# LCD.net
KiCad netlist of a schematic drawn in Altium Designer
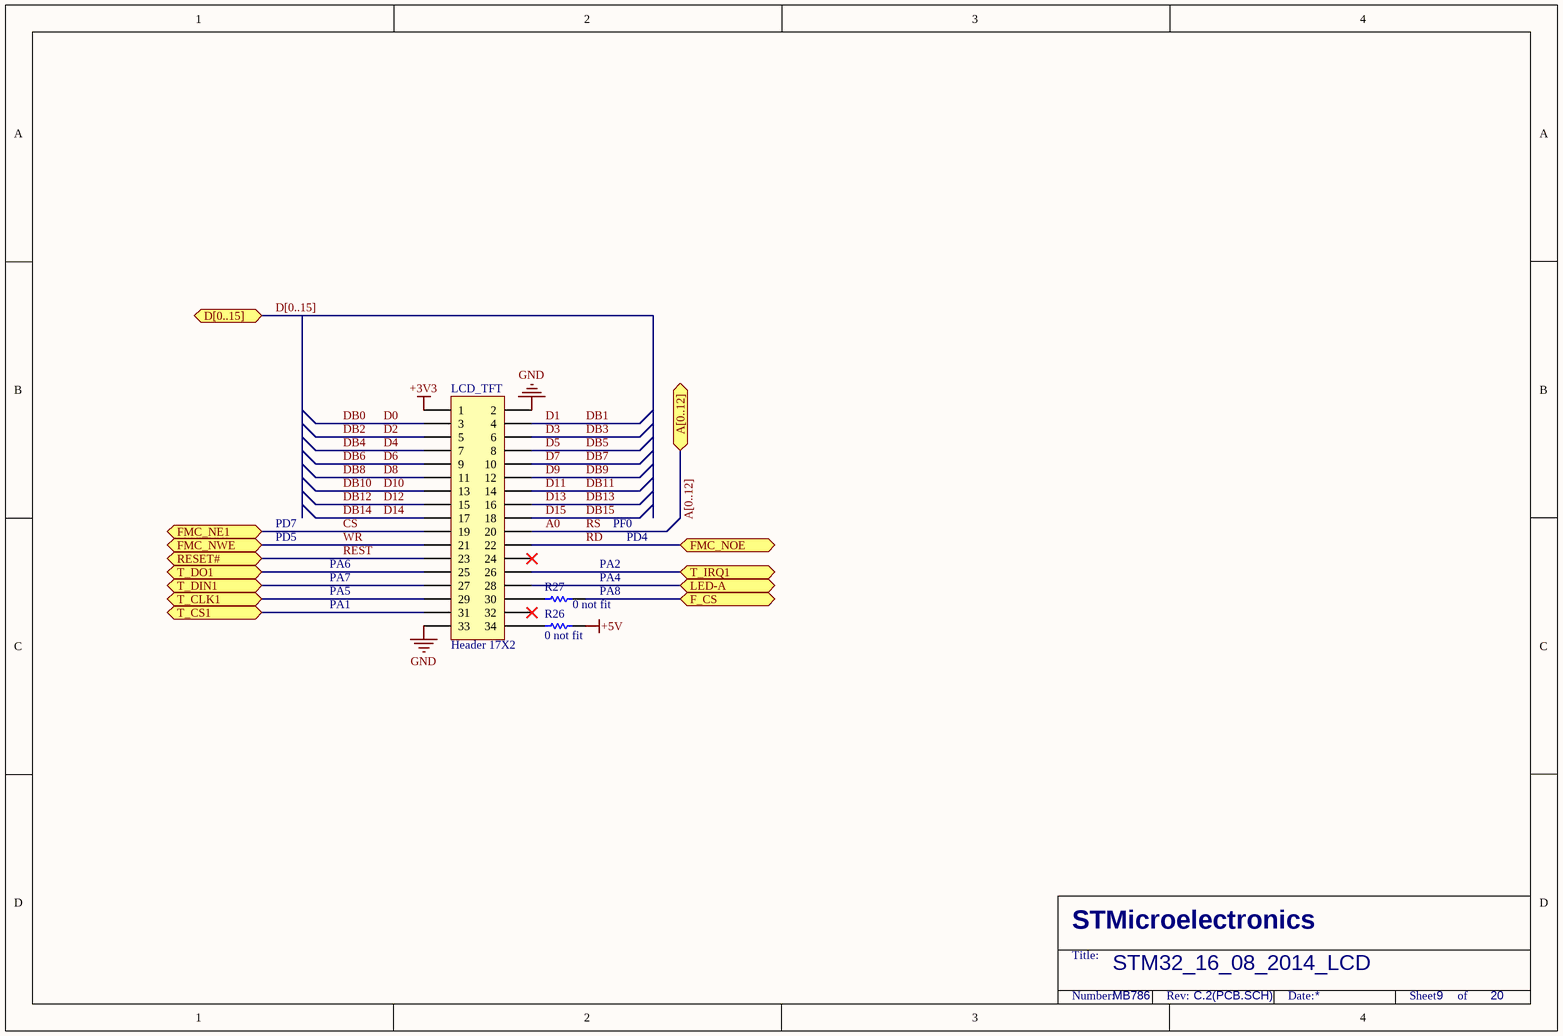
[diagram p0: LCD.SchDoc]

(export (version "E")
  (design (tool "Eeschema 10.0.6"))
  (components
    (comp (ref "LCD_TFT")
      (value "Header 17X2")
      (footprint "HDR2X17")
      (description "Header, 17-Pin, Dual row")
      (fields (field (name "PUBLISHER") "Altium Limited"))
      (libsource (lib "Miscellaneous Connectors") (part "Header 17X2"))
    )
    (comp (ref "R26")
      (value "0 not fit")
      (footprint "0603_R")
      (description "Resistor")
      (fields (field (name "PUBLISHER") "Altium Limited"))
      (libsource (lib "Miscellaneous Devices") (part "Res1"))
    )
    (comp (ref "R27")
      (value "0 not fit")
      (footprint "0603_R")
      (description "Resistor")
      (fields (field (name "PUBLISHER") "Altium Limited"))
      (libsource (lib "Miscellaneous Devices") (part "Res1"))
    )
  )
  (nets
    (net (code "13") (name "+3V3") (class "Default")
      (node (ref "LCD_TFT") (pin "1") (pinfunction "1_1") (pintype "passive"))
    )
    (net (code "14") (name "+5V") (class "Default")
      (node (ref "R26") (pin "1") (pinfunction "1_1") (pintype "passive"))
    )
    (net (code "15") (name "/A0") (class "Default")
      (node (ref "LCD_TFT") (pin "20") (pinfunction "20_20") (pintype "passive"))
    )
    (net (code "17") (name "/CS") (class "Default")
      (node (ref "LCD_TFT") (pin "19") (pinfunction "19_19") (pintype "passive"))
    )
    (net (code "18") (name "/D0") (class "Default")
      (node (ref "LCD_TFT") (pin "3") (pinfunction "3_3") (pintype "passive"))
    )
    (net (code "19") (name "/D1") (class "Default")
      (node (ref "LCD_TFT") (pin "4") (pinfunction "4_4") (pintype "passive"))
    )
    (net (code "20") (name "/D2") (class "Default")
      (node (ref "LCD_TFT") (pin "5") (pinfunction "5_5") (pintype "passive"))
    )
    (net (code "21") (name "/D3") (class "Default")
      (node (ref "LCD_TFT") (pin "6") (pinfunction "6_6") (pintype "passive"))
    )
    (net (code "22") (name "/D4") (class "Default")
      (node (ref "LCD_TFT") (pin "7") (pinfunction "7_7") (pintype "passive"))
    )
    (net (code "23") (name "/D5") (class "Default")
      (node (ref "LCD_TFT") (pin "8") (pinfunction "8_8") (pintype "passive"))
    )
    (net (code "24") (name "/D6") (class "Default")
      (node (ref "LCD_TFT") (pin "9") (pinfunction "9_9") (pintype "passive"))
    )
    (net (code "25") (name "/D7") (class "Default")
      (node (ref "LCD_TFT") (pin "10") (pinfunction "10_10") (pintype "passive"))
    )
    (net (code "26") (name "/D8") (class "Default")
      (node (ref "LCD_TFT") (pin "11") (pinfunction "11_11") (pintype "passive"))
    )
    (net (code "27") (name "/D9") (class "Default")
      (node (ref "LCD_TFT") (pin "12") (pinfunction "12_12") (pintype "passive"))
    )
    (net (code "28") (name "/D10") (class "Default")
      (node (ref "LCD_TFT") (pin "13") (pinfunction "13_13") (pintype "passive"))
    )
    (net (code "29") (name "/D11") (class "Default")
      (node (ref "LCD_TFT") (pin "14") (pinfunction "14_14") (pintype "passive"))
    )
    (net (code "30") (name "/D12") (class "Default")
      (node (ref "LCD_TFT") (pin "15") (pinfunction "15_15") (pintype "passive"))
    )
    (net (code "31") (name "/D13") (class "Default")
      (node (ref "LCD_TFT") (pin "16") (pinfunction "16_16") (pintype "passive"))
    )
    (net (code "32") (name "/D14") (class "Default")
      (node (ref "LCD_TFT") (pin "17") (pinfunction "17_17") (pintype "passive"))
    )
    (net (code "33") (name "/D15") (class "Default")
      (node (ref "LCD_TFT") (pin "18") (pinfunction "18_18") (pintype "passive"))
    )
    (net (code "35") (name "/F_CS") (class "Default")
      (node (ref "R27") (pin "1") (pinfunction "1_1") (pintype "passive"))
    )
    (net (code "36") (name "/LED-A") (class "Default")
      (node (ref "LCD_TFT") (pin "28") (pinfunction "28_28") (pintype "passive"))
    )
    (net (code "37") (name "/RD") (class "Default")
      (node (ref "LCD_TFT") (pin "22") (pinfunction "22_22") (pintype "passive"))
    )
    (net (code "38") (name "/REST") (class "Default")
      (node (ref "LCD_TFT") (pin "23") (pinfunction "23_23") (pintype "passive"))
    )
    (net (code "39") (name "/T_CLK1") (class "Default")
      (node (ref "LCD_TFT") (pin "29") (pinfunction "29_29") (pintype "passive"))
    )
    (net (code "40") (name "/T_CS1") (class "Default")
      (node (ref "LCD_TFT") (pin "31") (pinfunction "31_31") (pintype "passive"))
    )
    (net (code "41") (name "/T_DIN1") (class "Default")
      (node (ref "LCD_TFT") (pin "27") (pinfunction "27_27") (pintype "passive"))
    )
    (net (code "42") (name "/T_DO1") (class "Default")
      (node (ref "LCD_TFT") (pin "25") (pinfunction "25_25") (pintype "passive"))
    )
    (net (code "43") (name "/T_IRQ1") (class "Default")
      (node (ref "LCD_TFT") (pin "26") (pinfunction "26_26") (pintype "passive"))
    )
    (net (code "44") (name "/WR") (class "Default")
      (node (ref "LCD_TFT") (pin "21") (pinfunction "21_21") (pintype "passive"))
    )
    (net (code "45") (name "GND") (class "Default")
      (node (ref "LCD_TFT") (pin "2") (pinfunction "2_2") (pintype "passive"))
      (node (ref "LCD_TFT") (pin "33") (pinfunction "33_33") (pintype "passive"))
    )
    (net (code "46") (name "Net-(LCD_TFT-Pad30)") (class "Default")
      (node (ref "LCD_TFT") (pin "30") (pinfunction "30_30") (pintype "passive"))
      (node (ref "R27") (pin "2") (pinfunction "2_2") (pintype "passive"))
    )
    (net (code "47") (name "Net-(LCD_TFT-Pad34)") (class "Default")
      (node (ref "LCD_TFT") (pin "34") (pinfunction "34_34") (pintype "passive"))
      (node (ref "R26") (pin "2") (pinfunction "2_2") (pintype "passive"))
    )
    (net (code "48") (name "unconnected-(LCD_TFT-Pad24)") (class "Default")
      (node (ref "LCD_TFT") (pin "24") (pinfunction "24_24") (pintype "passive+no_connect"))
    )
    (net (code "49") (name "unconnected-(LCD_TFT-Pad32)") (class "Default")
      (node (ref "LCD_TFT") (pin "32") (pinfunction "32_32") (pintype "passive+no_connect"))
    )
  )
)
